# TEST_BATT_PANEL.net
KiCad netlist of a schematic drawn in EAGLE
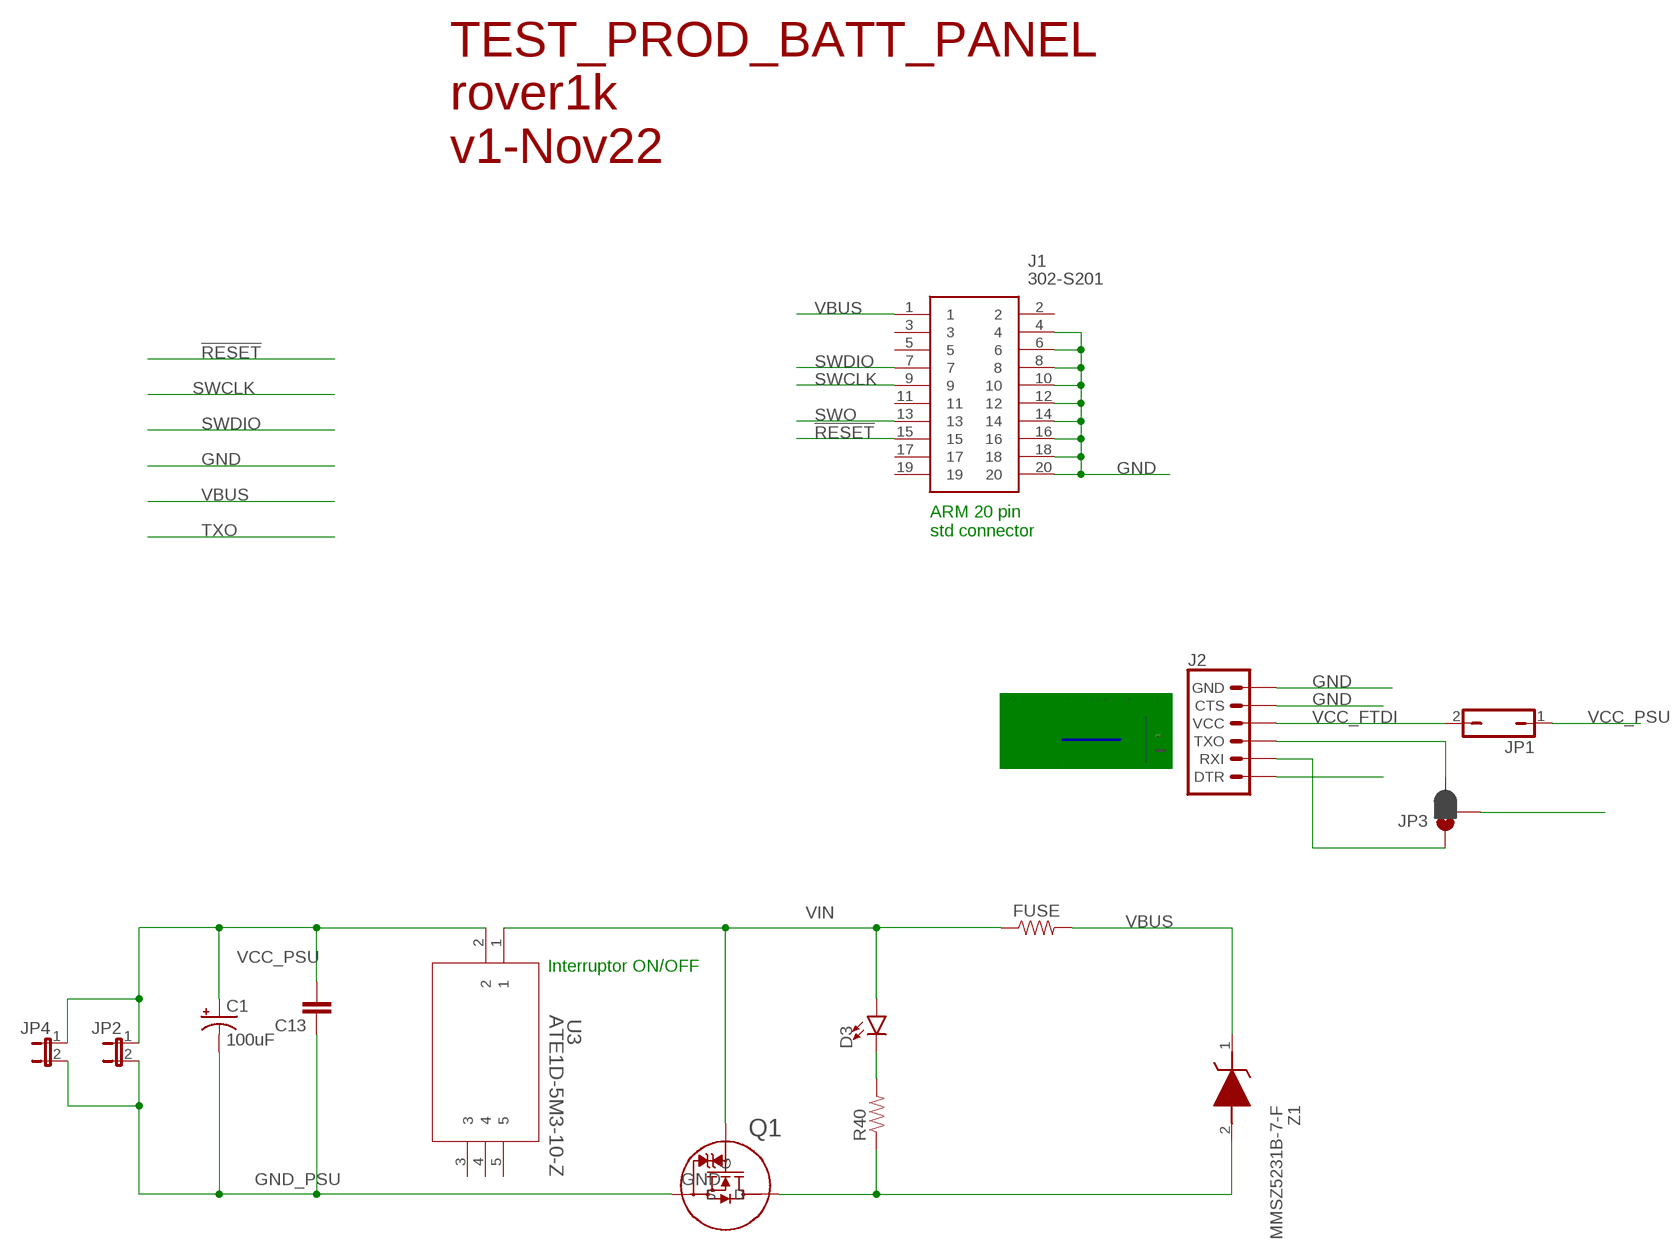
[diagram p0: schematic, sheet 1]

(export (version "E")
  (design (tool "Eeschema 10.0.6"))
  (components
    (comp (ref "C1")
      (value "100uF")
      (footprint "eagle-import:CPOL-RADIAL-2.5MM-6.5MM")
      (libsource (lib "eagle-import") (part "100UF-POLAR-RADIAL-2.5MM-25V-20%"))
    )
    (comp (ref "C13")
      (value "C-EUC0805")
      (footprint "eagle-import:C0805")
      (libsource (lib "eagle-import") (part "C-EUC0805"))
    )
    (comp (ref "D3")
      (value "LED3MM")
      (footprint "eagle-import:LED_3MM")
      (libsource (lib "eagle-import") (part "LED3MM"))
    )
    (comp (ref "FUSE")
      (value "RESISTOR0805")
      (footprint "eagle-import:0805")
      (libsource (lib "eagle-import") (part "RESISTOR0805"))
    )
    (comp (ref "J1")
      (value "302-S201")
      (footprint "eagle-import:SHDR20W66P254_2X10_3300X905X90")
      (libsource (lib "eagle-import") (part "302-S201"))
    )
    (comp (ref "J2")
      (value "6_PIN_SERIAL_TARGET")
      (footprint "eagle-import:1X06")
      (libsource (lib "eagle-import") (part "6_PIN_SERIAL_TARGET"))
    )
    (comp (ref "JP1")
      (value "JP1Q")
      (footprint "eagle-import:JP1")
      (libsource (lib "eagle-import") (part "JP1Q"))
    )
    (comp (ref "JP2")
      (value "JP1E")
      (footprint "eagle-import:JP1")
      (libsource (lib "eagle-import") (part "JP1E"))
    )
    (comp (ref "JP3")
      (value "JUMPER-SMT_3_1-NC_PASTE_NO-SILK")
      (footprint "eagle-import:SMT-JUMPER_3_1-NC_PASTE_NO-SILK")
      (libsource (lib "eagle-import") (part "JUMPER-SMT_3_1-NC_PASTE_NO-SILK"))
    )
    (comp (ref "JP4")
      (value "JP1E")
      (footprint "eagle-import:JP1")
      (libsource (lib "eagle-import") (part "JP1E"))
    )
    (comp (ref "Q1")
      (value "PJA3416AE_R1_00001")
      (footprint "eagle-import:SOT23_PJA3416_PNJ")
      (fields (field (name "COPYRIGHT") "Copyright (C) 2022 Ultra Librarian. All rights reserved."))
      (libsource (lib "eagle-import") (part "PJA3416AE_R1_00001"))
    )
    (comp (ref "R40")
      (value "10K")
      (footprint "eagle-import:0805")
      (libsource (lib "eagle-import") (part "RESISTOR0805-RES"))
    )
    (comp (ref "U3")
      (value "ATE1D-5M3-10-Z")
      (footprint "eagle-import:SPDT05_ATE1D_9P5X8_NDC")
      (fields (field (name "COPYRIGHT") "Copyright (C) 2022 Ultra Librarian. All rights reserved."))
      (libsource (lib "eagle-import") (part "ATE1D-5M3-10-Z"))
    )
    (comp (ref "Z1")
      (value "MMSZ5231B-7-F")
      (footprint "eagle-import:SOD3716X145N")
      (fields (field (name "MOUSER_PART_NUMBER") "621-MMSZ5231B-F"))
      (libsource (lib "eagle-import") (part "MMSZ5231B-7-F"))
    )
  )
  (nets
    (net (code "1") (name "/GND") (class "Default")
      (node (ref "J1") (pin "10") (pinfunction "10_10") (pintype "bidirectional"))
      (node (ref "J1") (pin "12") (pinfunction "12_12") (pintype "bidirectional"))
      (node (ref "J1") (pin "14") (pinfunction "14_14") (pintype "bidirectional"))
      (node (ref "J1") (pin "16") (pinfunction "16_16") (pintype "bidirectional"))
      (node (ref "J1") (pin "18") (pinfunction "18_18") (pintype "bidirectional"))
      (node (ref "J1") (pin "20") (pinfunction "20_20") (pintype "bidirectional"))
      (node (ref "J1") (pin "4") (pinfunction "4_4") (pintype "bidirectional"))
      (node (ref "J1") (pin "6") (pinfunction "6_6") (pintype "bidirectional"))
      (node (ref "J1") (pin "8") (pinfunction "8_8") (pintype "bidirectional"))
      (node (ref "J2") (pin "5") (pinfunction "CTS_5") (pintype "passive"))
      (node (ref "J2") (pin "6") (pinfunction "GND_6") (pintype "passive"))
      (node (ref "Q1") (pin "3") (pinfunction "D_3") (pintype "passive"))
      (node (ref "R40") (pin "1") (pinfunction "1_1") (pintype "passive"))
      (node (ref "Z1") (pin "2") (pinfunction "A_2") (pintype "bidirectional"))
    )
    (net (code "2") (name "/GND_PSU") (class "Default")
      (node (ref "C1") (pin "2") (pinfunction "-_2") (pintype "passive"))
      (node (ref "C13") (pin "1") (pinfunction "1_1") (pintype "passive"))
      (node (ref "JP2") (pin "2") (pinfunction "2_2") (pintype "passive"))
      (node (ref "JP4") (pin "2") (pinfunction "2_2") (pintype "passive"))
      (node (ref "Q1") (pin "2") (pinfunction "S_2") (pintype "passive"))
    )
    (net (code "3") (name "/SWCLK") (class "Default")
      (node (ref "J1") (pin "9") (pinfunction "9_9") (pintype "bidirectional"))
    )
    (net (code "4") (name "/SWDIO") (class "Default")
      (node (ref "J1") (pin "7") (pinfunction "7_7") (pintype "bidirectional"))
    )
    (net (code "5") (name "/SWO") (class "Default")
      (node (ref "J1") (pin "13") (pinfunction "13_13") (pintype "bidirectional"))
    )
    (net (code "6") (name "/TXO") (class "Default")
      (node (ref "JP3") (pin "2") (pinfunction "2_2") (pintype "passive"))
    )
    (net (code "7") (name "/VBUS") (class "Default")
      (node (ref "FUSE") (pin "2") (pinfunction "2_2") (pintype "passive"))
      (node (ref "J1") (pin "1") (pinfunction "1_1") (pintype "bidirectional"))
      (node (ref "Z1") (pin "1") (pinfunction "K_1") (pintype "bidirectional"))
    )
    (net (code "8") (name "/VCC_FTDI") (class "Default")
      (node (ref "J2") (pin "4") (pinfunction "VCC_4") (pintype "passive"))
      (node (ref "JP1") (pin "2") (pinfunction "2_2") (pintype "passive"))
    )
    (net (code "9") (name "/VCC_PSU") (class "Default")
      (node (ref "C1") (pin "1") (pinfunction "+_1") (pintype "passive"))
      (node (ref "C13") (pin "2") (pinfunction "2_2") (pintype "passive"))
      (node (ref "JP1") (pin "1") (pinfunction "1_1") (pintype "passive"))
      (node (ref "JP2") (pin "1") (pinfunction "1_1") (pintype "passive"))
      (node (ref "JP4") (pin "1") (pinfunction "1_1") (pintype "passive"))
      (node (ref "U3") (pin "2") (pinfunction "2_2") (pintype "passive"))
    )
    (net (code "10") (name "/VIN") (class "Default")
      (node (ref "D3") (pin "A") (pinfunction "A_A") (pintype "passive"))
      (node (ref "FUSE") (pin "1") (pinfunction "1_1") (pintype "passive"))
      (node (ref "Q1") (pin "1") (pinfunction "G_1") (pintype "passive"))
      (node (ref "U3") (pin "1") (pinfunction "1_1") (pintype "passive"))
    )
    (net (code "11") (name "/~{RESET}") (class "Default")
      (node (ref "J1") (pin "15") (pinfunction "15_15") (pintype "bidirectional"))
    )
    (net (code "12") (name "Net-(D3-C)") (class "Default")
      (node (ref "D3") (pin "K") (pinfunction "C_K") (pintype "passive"))
      (node (ref "R40") (pin "2") (pinfunction "2_2") (pintype "passive"))
    )
    (net (code "13") (name "Net-(J2-RXI)") (class "Default")
      (node (ref "J2") (pin "2") (pinfunction "RXI_2") (pintype "passive"))
      (node (ref "JP3") (pin "1") (pinfunction "1_1") (pintype "passive"))
    )
    (net (code "14") (name "Net-(J2-TXO)") (class "Default")
      (node (ref "J2") (pin "3") (pinfunction "TXO_3") (pintype "passive"))
      (node (ref "JP3") (pin "3") (pinfunction "3_3") (pintype "passive"))
    )
    (net (code "15") (name "unconnected-(J1-Pad2)") (class "Default")
      (node (ref "J1") (pin "2") (pinfunction "2_2") (pintype "bidirectional"))
    )
    (net (code "16") (name "unconnected-(J1-Pad3)") (class "Default")
      (node (ref "J1") (pin "3") (pinfunction "3_3") (pintype "bidirectional"))
    )
    (net (code "17") (name "unconnected-(J1-Pad5)") (class "Default")
      (node (ref "J1") (pin "5") (pinfunction "5_5") (pintype "bidirectional"))
    )
    (net (code "18") (name "unconnected-(J1-Pad11)") (class "Default")
      (node (ref "J1") (pin "11") (pinfunction "11_11") (pintype "bidirectional"))
    )
    (net (code "19") (name "unconnected-(J1-Pad17)") (class "Default")
      (node (ref "J1") (pin "17") (pinfunction "17_17") (pintype "bidirectional"))
    )
    (net (code "20") (name "unconnected-(J1-Pad19)") (class "Default")
      (node (ref "J1") (pin "19") (pinfunction "19_19") (pintype "bidirectional"))
    )
    (net (code "21") (name "unconnected-(J2-DTR-Pad1)") (class "Default")
      (node (ref "J2") (pin "1") (pinfunction "DTR_1") (pintype "passive"))
    )
    (net (code "22") (name "unconnected-(U3-Pad3)") (class "Default")
      (node (ref "U3") (pin "3") (pinfunction "3_3") (pintype "passive"))
    )
    (net (code "23") (name "unconnected-(U3-Pad4)") (class "Default")
      (node (ref "U3") (pin "4") (pinfunction "4_4") (pintype "passive"))
    )
    (net (code "24") (name "unconnected-(U3-Pad5)") (class "Default")
      (node (ref "U3") (pin "5") (pinfunction "5_5") (pintype "passive"))
    )
  )
)
